# 19_-CAMERA_PWR_CONNECTORS.net
KiCad netlist of a schematic drawn in Altium Designer
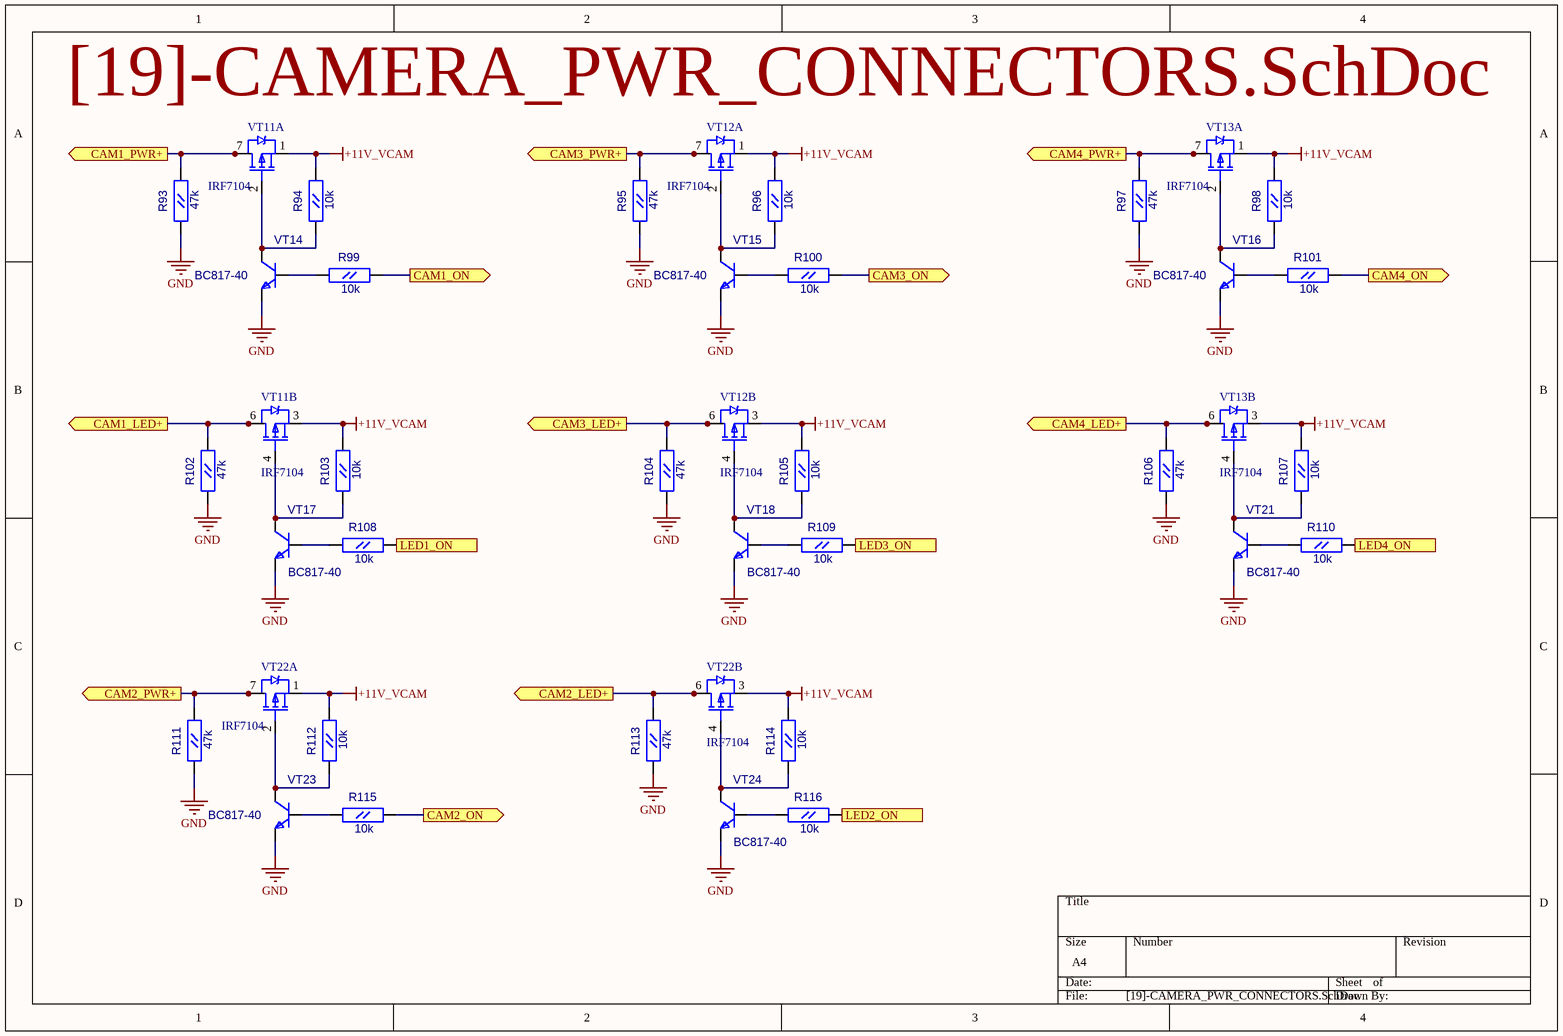
[diagram p0: [19]-CAMERA_PWR_CONNECTORS.SchDoc]

(export (version "E")
  (design (tool "Eeschema 10.0.6"))
  (components
    (comp (ref "R93")
      (value "47k")
      (footprint "RC0603")
      (description "RC0603")
      (libsource (lib "fizik_lib") (part "RC0603"))
    )
    (comp (ref "R94")
      (value "10k")
      (footprint "RC0603")
      (description "RC0603")
      (libsource (lib "fizik_lib") (part "RC0603"))
    )
    (comp (ref "R95")
      (value "47k")
      (footprint "RC0603")
      (description "RC0603")
      (libsource (lib "fizik_lib") (part "RC0603"))
    )
    (comp (ref "R96")
      (value "10k")
      (footprint "RC0603")
      (description "RC0603")
      (libsource (lib "fizik_lib") (part "RC0603"))
    )
    (comp (ref "R97")
      (value "47k")
      (footprint "RC0603")
      (description "RC0603")
      (libsource (lib "fizik_lib") (part "RC0603"))
    )
    (comp (ref "R98")
      (value "10k")
      (footprint "RC0603")
      (description "RC0603")
      (libsource (lib "fizik_lib") (part "RC0603"))
    )
    (comp (ref "R99")
      (value "10k")
      (footprint "RC0603")
      (description "RC0603")
      (libsource (lib "fizik_lib") (part "RC0603"))
    )
    (comp (ref "R100")
      (value "10k")
      (footprint "RC0603")
      (description "RC0603")
      (libsource (lib "fizik_lib") (part "RC0603"))
    )
    (comp (ref "R101")
      (value "10k")
      (footprint "RC0603")
      (description "RC0603")
      (libsource (lib "fizik_lib") (part "RC0603"))
    )
    (comp (ref "R102")
      (value "47k")
      (footprint "RC0603")
      (description "RC0603")
      (libsource (lib "fizik_lib") (part "RC0603"))
    )
    (comp (ref "R103")
      (value "10k")
      (footprint "RC0603")
      (description "RC0603")
      (libsource (lib "fizik_lib") (part "RC0603"))
    )
    (comp (ref "R104")
      (value "47k")
      (footprint "RC0603")
      (description "RC0603")
      (libsource (lib "fizik_lib") (part "RC0603"))
    )
    (comp (ref "R105")
      (value "10k")
      (footprint "RC0603")
      (description "RC0603")
      (libsource (lib "fizik_lib") (part "RC0603"))
    )
    (comp (ref "R106")
      (value "47k")
      (footprint "RC0603")
      (description "RC0603")
      (libsource (lib "fizik_lib") (part "RC0603"))
    )
    (comp (ref "R107")
      (value "10k")
      (footprint "RC0603")
      (description "RC0603")
      (libsource (lib "fizik_lib") (part "RC0603"))
    )
    (comp (ref "R108")
      (value "10k")
      (footprint "RC0603")
      (description "RC0603")
      (libsource (lib "fizik_lib") (part "RC0603"))
    )
    (comp (ref "R109")
      (value "10k")
      (footprint "RC0603")
      (description "RC0603")
      (libsource (lib "fizik_lib") (part "RC0603"))
    )
    (comp (ref "R110")
      (value "10k")
      (footprint "RC0603")
      (description "RC0603")
      (libsource (lib "fizik_lib") (part "RC0603"))
    )
    (comp (ref "R111")
      (value "47k")
      (footprint "RC0603")
      (description "RC0603")
      (libsource (lib "fizik_lib") (part "RC0603"))
    )
    (comp (ref "R112")
      (value "10k")
      (footprint "RC0603")
      (description "RC0603")
      (libsource (lib "fizik_lib") (part "RC0603"))
    )
    (comp (ref "R113")
      (value "47k")
      (footprint "RC0603")
      (description "RC0603")
      (libsource (lib "fizik_lib") (part "RC0603"))
    )
    (comp (ref "R114")
      (value "10k")
      (footprint "RC0603")
      (description "RC0603")
      (libsource (lib "fizik_lib") (part "RC0603"))
    )
    (comp (ref "R115")
      (value "10k")
      (footprint "RC0603")
      (description "RC0603")
      (libsource (lib "fizik_lib") (part "RC0603"))
    )
    (comp (ref "R116")
      (value "10k")
      (footprint "RC0603")
      (description "RC0603")
      (libsource (lib "fizik_lib") (part "RC0603"))
    )
    (comp (ref "VT11")
      (value "IRF7104")
      (footprint "SO-8")
      (description "Dual P-channel MOSFET. 20V,2.3A, 0.25Ohm")
      (libsource (lib "fizik_lib (1)") (part "IRF7104"))
    )
    (comp (ref "VT12")
      (value "IRF7104")
      (footprint "SO-8")
      (description "Dual P-channel MOSFET. 20V,2.3A, 0.25Ohm")
      (libsource (lib "fizik_lib (1)") (part "IRF7104"))
    )
    (comp (ref "VT13")
      (value "IRF7104")
      (footprint "SO-8")
      (description "Dual P-channel MOSFET. 20V,2.3A, 0.25Ohm")
      (libsource (lib "fizik_lib (1)") (part "IRF7104"))
    )
    (comp (ref "VT14")
      (value "BC817-40")
      (footprint "SOT-23(123)")
      (description "NPN 500ma transistor")
      (libsource (lib "fizik_lib") (part "BC846BLT1"))
    )
    (comp (ref "VT15")
      (value "BC817-40")
      (footprint "SOT-23(123)")
      (description "NPN 500ma transistor")
      (libsource (lib "fizik_lib") (part "BC846BLT1"))
    )
    (comp (ref "VT16")
      (value "BC817-40")
      (footprint "SOT-23(123)")
      (description "NPN 500ma transistor")
      (libsource (lib "fizik_lib") (part "BC846BLT1"))
    )
    (comp (ref "VT17")
      (value "BC817-40")
      (footprint "SOT-23(123)")
      (description "NPN 500ma transistor")
      (libsource (lib "fizik_lib") (part "BC846BLT1"))
    )
    (comp (ref "VT18")
      (value "BC817-40")
      (footprint "SOT-23(123)")
      (description "NPN 500ma transistor")
      (libsource (lib "fizik_lib") (part "BC846BLT1"))
    )
    (comp (ref "VT21")
      (value "BC817-40")
      (footprint "SOT-23(123)")
      (description "NPN 500ma transistor")
      (libsource (lib "fizik_lib") (part "BC846BLT1"))
    )
    (comp (ref "VT22")
      (value "IRF7104")
      (footprint "SO-8")
      (description "Dual P-channel MOSFET. 20V,2.3A, 0.25Ohm")
      (libsource (lib "fizik_lib (1)") (part "IRF7104"))
    )
    (comp (ref "VT23")
      (value "BC817-40")
      (footprint "SOT-23(123)")
      (description "NPN 500ma transistor")
      (libsource (lib "fizik_lib") (part "BC846BLT1"))
    )
    (comp (ref "VT24")
      (value "BC817-40")
      (footprint "SOT-23(123)")
      (description "NPN 500ma transistor")
      (libsource (lib "fizik_lib") (part "BC846BLT1"))
    )
  )
  (nets
    (net (code "1") (name "+11V_VCAM") (class "Default")
      (node (ref "R103") (pin "2") (pinfunction "B_2") (pintype "passive"))
      (node (ref "R105") (pin "2") (pinfunction "B_2") (pintype "passive"))
      (node (ref "R107") (pin "2") (pinfunction "B_2") (pintype "passive"))
      (node (ref "R112") (pin "2") (pinfunction "B_2") (pintype "passive"))
      (node (ref "R114") (pin "2") (pinfunction "B_2") (pintype "passive"))
      (node (ref "R94") (pin "2") (pinfunction "B_2") (pintype "passive"))
      (node (ref "R96") (pin "2") (pinfunction "B_2") (pintype "passive"))
      (node (ref "R98") (pin "2") (pinfunction "B_2") (pintype "passive"))
      (node (ref "VT11") (pin "1") (pinfunction "S_1") (pintype "passive"))
      (node (ref "VT11") (pin "3") (pinfunction "S_3") (pintype "passive"))
      (node (ref "VT12") (pin "1") (pinfunction "S_1") (pintype "passive"))
      (node (ref "VT12") (pin "3") (pinfunction "S_3") (pintype "passive"))
      (node (ref "VT13") (pin "1") (pinfunction "S_1") (pintype "passive"))
      (node (ref "VT13") (pin "3") (pinfunction "S_3") (pintype "passive"))
      (node (ref "VT22") (pin "1") (pinfunction "S_1") (pintype "passive"))
      (node (ref "VT22") (pin "3") (pinfunction "S_3") (pintype "passive"))
    )
    (net (code "2") (name "/CAM1_LED+") (class "Default")
      (node (ref "R102") (pin "2") (pinfunction "B_2") (pintype "passive"))
      (node (ref "VT11") (pin "5") (pinfunction "5_5") (pintype "passive"))
      (node (ref "VT11") (pin "6") (pinfunction "D_6") (pintype "passive"))
    )
    (net (code "3") (name "/CAM1_ON") (class "Default")
      (node (ref "R99") (pin "2") (pinfunction "B_2") (pintype "passive"))
    )
    (net (code "4") (name "/CAM1_PWR+") (class "Default")
      (node (ref "R93") (pin "2") (pinfunction "B_2") (pintype "passive"))
      (node (ref "VT11") (pin "7") (pinfunction "D_7") (pintype "passive"))
      (node (ref "VT11") (pin "8") (pinfunction "8_8") (pintype "passive"))
    )
    (net (code "5") (name "/CAM2_LED+") (class "Default")
      (node (ref "R113") (pin "2") (pinfunction "B_2") (pintype "passive"))
      (node (ref "VT22") (pin "5") (pinfunction "5_5") (pintype "passive"))
      (node (ref "VT22") (pin "6") (pinfunction "D_6") (pintype "passive"))
    )
    (net (code "6") (name "/CAM2_ON") (class "Default")
      (node (ref "R115") (pin "2") (pinfunction "B_2") (pintype "passive"))
    )
    (net (code "7") (name "/CAM2_PWR+") (class "Default")
      (node (ref "R111") (pin "2") (pinfunction "B_2") (pintype "passive"))
      (node (ref "VT22") (pin "7") (pinfunction "D_7") (pintype "passive"))
      (node (ref "VT22") (pin "8") (pinfunction "8_8") (pintype "passive"))
    )
    (net (code "8") (name "/CAM3_LED+") (class "Default")
      (node (ref "R104") (pin "2") (pinfunction "B_2") (pintype "passive"))
      (node (ref "VT12") (pin "5") (pinfunction "5_5") (pintype "passive"))
      (node (ref "VT12") (pin "6") (pinfunction "D_6") (pintype "passive"))
    )
    (net (code "9") (name "/CAM3_ON") (class "Default")
      (node (ref "R100") (pin "2") (pinfunction "B_2") (pintype "passive"))
    )
    (net (code "10") (name "/CAM3_PWR+") (class "Default")
      (node (ref "R95") (pin "2") (pinfunction "B_2") (pintype "passive"))
      (node (ref "VT12") (pin "7") (pinfunction "D_7") (pintype "passive"))
      (node (ref "VT12") (pin "8") (pinfunction "8_8") (pintype "passive"))
    )
    (net (code "11") (name "/CAM4_LED+") (class "Default")
      (node (ref "R106") (pin "2") (pinfunction "B_2") (pintype "passive"))
      (node (ref "VT13") (pin "5") (pinfunction "5_5") (pintype "passive"))
      (node (ref "VT13") (pin "6") (pinfunction "D_6") (pintype "passive"))
    )
    (net (code "12") (name "/CAM4_ON") (class "Default")
      (node (ref "R101") (pin "2") (pinfunction "B_2") (pintype "passive"))
    )
    (net (code "13") (name "/CAM4_PWR+") (class "Default")
      (node (ref "R97") (pin "2") (pinfunction "B_2") (pintype "passive"))
      (node (ref "VT13") (pin "7") (pinfunction "D_7") (pintype "passive"))
      (node (ref "VT13") (pin "8") (pinfunction "8_8") (pintype "passive"))
    )
    (net (code "14") (name "/LED1_ON") (class "Default")
      (node (ref "R108") (pin "2") (pinfunction "B_2") (pintype "passive"))
    )
    (net (code "15") (name "/LED2_ON") (class "Default")
      (node (ref "R116") (pin "2") (pinfunction "B_2") (pintype "passive"))
    )
    (net (code "16") (name "/LED3_ON") (class "Default")
      (node (ref "R109") (pin "2") (pinfunction "B_2") (pintype "passive"))
    )
    (net (code "17") (name "/LED4_ON") (class "Default")
      (node (ref "R110") (pin "2") (pinfunction "B_2") (pintype "passive"))
    )
    (net (code "18") (name "GND") (class "Default")
      (node (ref "R102") (pin "1") (pinfunction "A_1") (pintype "passive"))
      (node (ref "R104") (pin "1") (pinfunction "A_1") (pintype "passive"))
      (node (ref "R106") (pin "1") (pinfunction "A_1") (pintype "passive"))
      (node (ref "R111") (pin "1") (pinfunction "A_1") (pintype "passive"))
      (node (ref "R113") (pin "1") (pinfunction "A_1") (pintype "passive"))
      (node (ref "R93") (pin "1") (pinfunction "A_1") (pintype "passive"))
      (node (ref "R95") (pin "1") (pinfunction "A_1") (pintype "passive"))
      (node (ref "R97") (pin "1") (pinfunction "A_1") (pintype "passive"))
      (node (ref "VT14") (pin "2") (pinfunction "E_2") (pintype "passive"))
      (node (ref "VT15") (pin "2") (pinfunction "E_2") (pintype "passive"))
      (node (ref "VT16") (pin "2") (pinfunction "E_2") (pintype "passive"))
      (node (ref "VT17") (pin "2") (pinfunction "E_2") (pintype "passive"))
      (node (ref "VT18") (pin "2") (pinfunction "E_2") (pintype "passive"))
      (node (ref "VT21") (pin "2") (pinfunction "E_2") (pintype "passive"))
      (node (ref "VT23") (pin "2") (pinfunction "E_2") (pintype "passive"))
      (node (ref "VT24") (pin "2") (pinfunction "E_2") (pintype "passive"))
    )
    (net (code "19") (name "Net-(R94-A)") (class "Default")
      (node (ref "R94") (pin "1") (pinfunction "A_1") (pintype "passive"))
      (node (ref "VT11") (pin "2") (pinfunction "G_2") (pintype "passive"))
      (node (ref "VT14") (pin "3") (pinfunction "C_3") (pintype "passive"))
    )
    (net (code "20") (name "Net-(R96-A)") (class "Default")
      (node (ref "R96") (pin "1") (pinfunction "A_1") (pintype "passive"))
      (node (ref "VT12") (pin "2") (pinfunction "G_2") (pintype "passive"))
      (node (ref "VT15") (pin "3") (pinfunction "C_3") (pintype "passive"))
    )
    (net (code "21") (name "Net-(R98-A)") (class "Default")
      (node (ref "R98") (pin "1") (pinfunction "A_1") (pintype "passive"))
      (node (ref "VT13") (pin "2") (pinfunction "G_2") (pintype "passive"))
      (node (ref "VT16") (pin "3") (pinfunction "C_3") (pintype "passive"))
    )
    (net (code "22") (name "Net-(R99-A)") (class "Default")
      (node (ref "R99") (pin "1") (pinfunction "A_1") (pintype "passive"))
      (node (ref "VT14") (pin "1") (pinfunction "B_1") (pintype "passive"))
    )
    (net (code "23") (name "Net-(R100-A)") (class "Default")
      (node (ref "R100") (pin "1") (pinfunction "A_1") (pintype "passive"))
      (node (ref "VT15") (pin "1") (pinfunction "B_1") (pintype "passive"))
    )
    (net (code "24") (name "Net-(R101-A)") (class "Default")
      (node (ref "R101") (pin "1") (pinfunction "A_1") (pintype "passive"))
      (node (ref "VT16") (pin "1") (pinfunction "B_1") (pintype "passive"))
    )
    (net (code "25") (name "Net-(R103-A)") (class "Default")
      (node (ref "R103") (pin "1") (pinfunction "A_1") (pintype "passive"))
      (node (ref "VT11") (pin "4") (pinfunction "G_4") (pintype "passive"))
      (node (ref "VT17") (pin "3") (pinfunction "C_3") (pintype "passive"))
    )
    (net (code "26") (name "Net-(R105-A)") (class "Default")
      (node (ref "R105") (pin "1") (pinfunction "A_1") (pintype "passive"))
      (node (ref "VT12") (pin "4") (pinfunction "G_4") (pintype "passive"))
      (node (ref "VT18") (pin "3") (pinfunction "C_3") (pintype "passive"))
    )
    (net (code "27") (name "Net-(R107-A)") (class "Default")
      (node (ref "R107") (pin "1") (pinfunction "A_1") (pintype "passive"))
      (node (ref "VT13") (pin "4") (pinfunction "G_4") (pintype "passive"))
      (node (ref "VT21") (pin "3") (pinfunction "C_3") (pintype "passive"))
    )
    (net (code "28") (name "Net-(R108-A)") (class "Default")
      (node (ref "R108") (pin "1") (pinfunction "A_1") (pintype "passive"))
      (node (ref "VT17") (pin "1") (pinfunction "B_1") (pintype "passive"))
    )
    (net (code "29") (name "Net-(R109-A)") (class "Default")
      (node (ref "R109") (pin "1") (pinfunction "A_1") (pintype "passive"))
      (node (ref "VT18") (pin "1") (pinfunction "B_1") (pintype "passive"))
    )
    (net (code "30") (name "Net-(R110-A)") (class "Default")
      (node (ref "R110") (pin "1") (pinfunction "A_1") (pintype "passive"))
      (node (ref "VT21") (pin "1") (pinfunction "B_1") (pintype "passive"))
    )
    (net (code "31") (name "Net-(R112-A)") (class "Default")
      (node (ref "R112") (pin "1") (pinfunction "A_1") (pintype "passive"))
      (node (ref "VT22") (pin "2") (pinfunction "G_2") (pintype "passive"))
      (node (ref "VT23") (pin "3") (pinfunction "C_3") (pintype "passive"))
    )
    (net (code "32") (name "Net-(R114-A)") (class "Default")
      (node (ref "R114") (pin "1") (pinfunction "A_1") (pintype "passive"))
      (node (ref "VT22") (pin "4") (pinfunction "G_4") (pintype "passive"))
      (node (ref "VT24") (pin "3") (pinfunction "C_3") (pintype "passive"))
    )
    (net (code "33") (name "Net-(R115-A)") (class "Default")
      (node (ref "R115") (pin "1") (pinfunction "A_1") (pintype "passive"))
      (node (ref "VT23") (pin "1") (pinfunction "B_1") (pintype "passive"))
    )
    (net (code "34") (name "Net-(R116-A)") (class "Default")
      (node (ref "R116") (pin "1") (pinfunction "A_1") (pintype "passive"))
      (node (ref "VT24") (pin "1") (pinfunction "B_1") (pintype "passive"))
    )
  )
)
